# STM32.net
KiCad netlist of a schematic drawn in Altium Designer
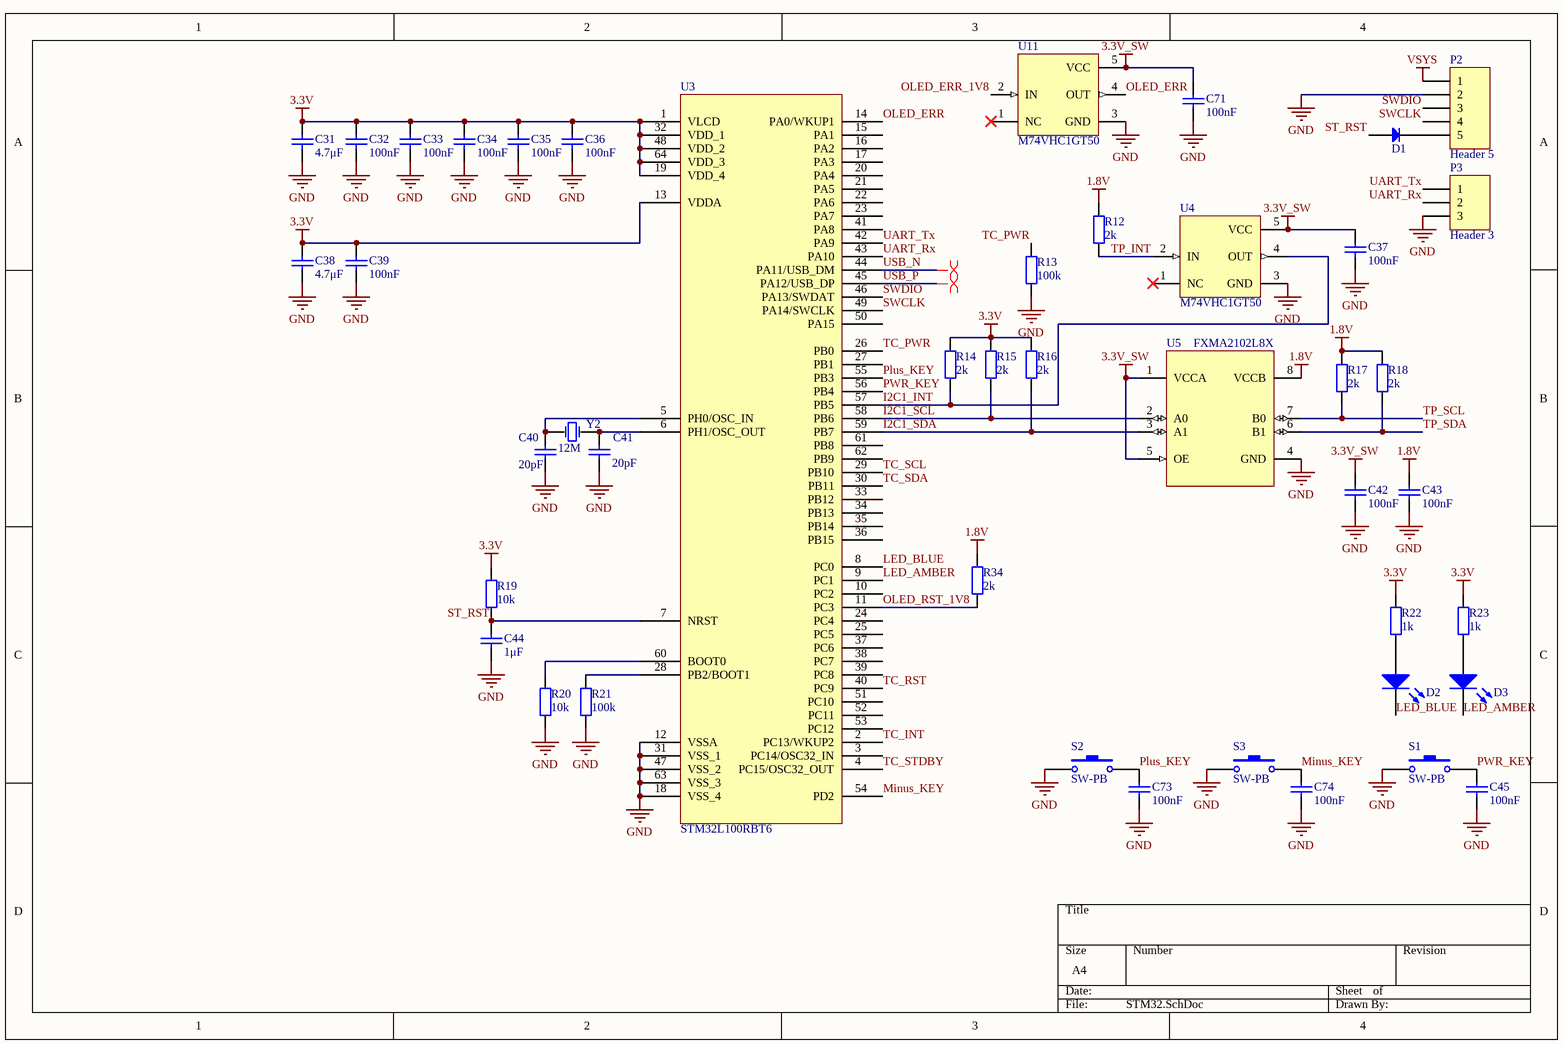
[diagram p0: STM32.SchDoc]

(export (version "E")
  (design (tool "Eeschema 10.0.6"))
  (components
    (comp (ref "C31")
      (value "4.7μF")
      (footprint "0402C")
      (description "无极性电容")
      (fields (field (name "Comment") "Cap") (field (name "PUBLISHER") "Altium Limited"))
      (libsource (lib "Huskie") (part "Cap"))
    )
    (comp (ref "C32")
      (value "100nF")
      (footprint "0402C")
      (description "无极性电容")
      (fields (field (name "Comment") "Cap") (field (name "PUBLISHER") "Altium Limited"))
      (libsource (lib "Huskie") (part "Cap"))
    )
    (comp (ref "C33")
      (value "100nF")
      (footprint "0402C")
      (description "无极性电容")
      (fields (field (name "Comment") "Cap") (field (name "PUBLISHER") "Altium Limited"))
      (libsource (lib "Huskie") (part "Cap"))
    )
    (comp (ref "C34")
      (value "100nF")
      (footprint "0402C")
      (description "无极性电容")
      (fields (field (name "Comment") "Cap") (field (name "PUBLISHER") "Altium Limited"))
      (libsource (lib "Huskie") (part "Cap"))
    )
    (comp (ref "C35")
      (value "100nF")
      (footprint "0402C")
      (description "无极性电容")
      (fields (field (name "Comment") "Cap") (field (name "PUBLISHER") "Altium Limited"))
      (libsource (lib "Huskie") (part "Cap"))
    )
    (comp (ref "C36")
      (value "100nF")
      (footprint "0402C")
      (description "无极性电容")
      (fields (field (name "Comment") "Cap") (field (name "PUBLISHER") "Altium Limited"))
      (libsource (lib "Huskie") (part "Cap"))
    )
    (comp (ref "C37")
      (value "100nF")
      (footprint "0402C")
      (description "无极性电容")
      (fields (field (name "Comment") "Cap") (field (name "PUBLISHER") "Altium Limited"))
      (libsource (lib "Huskie") (part "Cap"))
    )
    (comp (ref "C38")
      (value "4.7μF")
      (footprint "0402C")
      (description "无极性电容")
      (fields (field (name "Comment") "Cap") (field (name "PUBLISHER") "Altium Limited"))
      (libsource (lib "Huskie") (part "Cap"))
    )
    (comp (ref "C39")
      (value "100nF")
      (footprint "0402C")
      (description "无极性电容")
      (fields (field (name "Comment") "Cap") (field (name "PUBLISHER") "Altium Limited"))
      (libsource (lib "Huskie") (part "Cap"))
    )
    (comp (ref "C40")
      (value "20pF")
      (footprint "0402C")
      (description "无极性电容")
      (fields (field (name "Comment") "Cap") (field (name "PUBLISHER") "Altium Limited"))
      (libsource (lib "Huskie") (part "Cap"))
    )
    (comp (ref "C41")
      (value "20pF")
      (footprint "0402C")
      (description "无极性电容")
      (fields (field (name "Comment") "Cap") (field (name "PUBLISHER") "Altium Limited"))
      (libsource (lib "Huskie") (part "Cap"))
    )
    (comp (ref "C42")
      (value "100nF")
      (footprint "0402C")
      (description "无极性电容")
      (fields (field (name "Comment") "Cap") (field (name "PUBLISHER") "Altium Limited"))
      (libsource (lib "Huskie") (part "Cap"))
    )
    (comp (ref "C43")
      (value "100nF")
      (footprint "0402C")
      (description "无极性电容")
      (fields (field (name "Comment") "Cap") (field (name "PUBLISHER") "Altium Limited"))
      (libsource (lib "Huskie") (part "Cap"))
    )
    (comp (ref "C44")
      (value "1μF")
      (footprint "0402C")
      (description "无极性电容")
      (fields (field (name "Comment") "Cap") (field (name "PUBLISHER") "Altium Limited"))
      (libsource (lib "Huskie") (part "Cap"))
    )
    (comp (ref "C45")
      (value "100nF")
      (footprint "0402C")
      (description "无极性电容")
      (fields (field (name "Comment") "Cap") (field (name "PUBLISHER") "Altium Limited"))
      (libsource (lib "Huskie") (part "Cap"))
    )
    (comp (ref "C71")
      (value "100nF")
      (footprint "0402C")
      (description "无极性电容")
      (fields (field (name "Comment") "Cap") (field (name "PUBLISHER") "Altium Limited"))
      (libsource (lib "Huskie") (part "Cap"))
    )
    (comp (ref "C73")
      (value "100nF")
      (footprint "0402C")
      (description "无极性电容")
      (fields (field (name "Comment") "Cap") (field (name "PUBLISHER") "Altium Limited"))
      (libsource (lib "Huskie") (part "Cap"))
    )
    (comp (ref "C74")
      (value "100nF")
      (footprint "0402C")
      (description "无极性电容")
      (fields (field (name "Comment") "Cap") (field (name "PUBLISHER") "Altium Limited"))
      (libsource (lib "Huskie") (part "Cap"))
    )
    (comp (ref "D1")
      (value "Diode")
      (footprint "SOD-323")
      (description "二极管")
      (fields (field (name "PUBLISHER") "Altium Limited"))
      (libsource (lib "Huskie") (part "Diode"))
    )
    (comp (ref "D2")
      (value "LED0")
      (footprint "0603LED")
      (description "发光二极管")
      (fields (field (name "PUBLISHER") "Altium Limited"))
      (libsource (lib "Huskie") (part "LED0"))
    )
    (comp (ref "D3")
      (value "LED0")
      (footprint "0603LED")
      (description "发光二极管")
      (fields (field (name "PUBLISHER") "Altium Limited"))
      (libsource (lib "Huskie") (part "LED0"))
    )
    (comp (ref "P2")
      (value "Header 5")
      (footprint "HDR1X5")
      (description "Header, 5-Pin")
      (fields (field (name "PUBLISHER") "Altium Limited"))
      (libsource (lib "Miscellaneous Connectors") (part "Header 5"))
    )
    (comp (ref "P3")
      (value "Header 3")
      (footprint "HDR1X3")
      (description "Header, 3-Pin")
      (fields (field (name "PUBLISHER") "Altium Limited"))
      (libsource (lib "Miscellaneous Connectors") (part "Header 3"))
    )
    (comp (ref "R12")
      (value "2k")
      (footprint "0402R")
      (description "电阻")
      (fields (field (name "Comment") "Resistor") (field (name "PUBLISHER") "Altium Limited"))
      (libsource (lib "Huskie") (part "Resistor"))
    )
    (comp (ref "R13")
      (value "100k")
      (footprint "0402R")
      (description "电阻")
      (fields (field (name "Comment") "Resistor") (field (name "PUBLISHER") "Altium Limited"))
      (libsource (lib "Huskie") (part "Resistor"))
    )
    (comp (ref "R14")
      (value "2k")
      (footprint "0402R")
      (description "电阻")
      (fields (field (name "Comment") "Resistor") (field (name "PUBLISHER") "Altium Limited"))
      (libsource (lib "Huskie") (part "Resistor"))
    )
    (comp (ref "R15")
      (value "2k")
      (footprint "0402R")
      (description "电阻")
      (fields (field (name "Comment") "Resistor") (field (name "PUBLISHER") "Altium Limited"))
      (libsource (lib "Huskie") (part "Resistor"))
    )
    (comp (ref "R16")
      (value "2k")
      (footprint "0402R")
      (description "电阻")
      (fields (field (name "Comment") "Resistor") (field (name "PUBLISHER") "Altium Limited"))
      (libsource (lib "Huskie") (part "Resistor"))
    )
    (comp (ref "R17")
      (value "2k")
      (footprint "0402R")
      (description "电阻")
      (fields (field (name "Comment") "Resistor") (field (name "PUBLISHER") "Altium Limited"))
      (libsource (lib "Huskie") (part "Resistor"))
    )
    (comp (ref "R18")
      (value "2k")
      (footprint "0402R")
      (description "电阻")
      (fields (field (name "Comment") "Resistor") (field (name "PUBLISHER") "Altium Limited"))
      (libsource (lib "Huskie") (part "Resistor"))
    )
    (comp (ref "R19")
      (value "10k")
      (footprint "0402R")
      (description "电阻")
      (fields (field (name "Comment") "Resistor") (field (name "PUBLISHER") "Altium Limited"))
      (libsource (lib "Huskie") (part "Resistor"))
    )
    (comp (ref "R20")
      (value "10k")
      (footprint "0402R")
      (description "电阻")
      (fields (field (name "Comment") "Resistor") (field (name "PUBLISHER") "Altium Limited"))
      (libsource (lib "Huskie") (part "Resistor"))
    )
    (comp (ref "R21")
      (value "100k")
      (footprint "0402R")
      (description "电阻")
      (fields (field (name "Comment") "Resistor") (field (name "PUBLISHER") "Altium Limited"))
      (libsource (lib "Huskie") (part "Resistor"))
    )
    (comp (ref "R22")
      (value "1k")
      (footprint "0402R")
      (description "电阻")
      (fields (field (name "Comment") "Resistor") (field (name "PUBLISHER") "Altium Limited"))
      (libsource (lib "Huskie") (part "Resistor"))
    )
    (comp (ref "R23")
      (value "1k")
      (footprint "0402R")
      (description "电阻")
      (fields (field (name "Comment") "Resistor") (field (name "PUBLISHER") "Altium Limited"))
      (libsource (lib "Huskie") (part "Resistor"))
    )
    (comp (ref "R34")
      (value "2k")
      (footprint "0402R")
      (description "电阻")
      (fields (field (name "Comment") "Resistor") (field (name "PUBLISHER") "Altium Limited"))
      (libsource (lib "Huskie") (part "Resistor"))
    )
    (comp (ref "S1")
      (value "SW-PB")
      (footprint "SW-TS-TL3330E")
      (description "微动开关")
      (fields (field (name "PUBLISHER") "Altium Limited"))
      (libsource (lib "Huskie") (part "SW-PB"))
    )
    (comp (ref "S2")
      (value "SW-PB")
      (footprint "SW-TS-TL3330E")
      (description "微动开关")
      (fields (field (name "PUBLISHER") "Altium Limited"))
      (libsource (lib "Huskie") (part "SW-PB"))
    )
    (comp (ref "S3")
      (value "SW-PB")
      (footprint "SW-TS-TL3330E")
      (description "微动开关")
      (fields (field (name "PUBLISHER") "Altium Limited"))
      (libsource (lib "Huskie") (part "SW-PB"))
    )
    (comp (ref "U3")
      (value "STM32L100RBT6")
      (footprint "LQFP-64")
      (description "IC, STM32L MICROCONTROLLER, ARM CORTEX M3")
      (fields (field (name "MANUFACTURER") "ST MICROELECTRONICS"))
      (libsource (lib "Huskie") (part "STM32L100RBT6"))
    )
    (comp (ref "U4")
      (value "M74VHC1GT50")
      (footprint "SC-70(SC-70-5)")
      (description "IC, NON-INVERTING BUFFER, CMOS LOGIC LEVEL SHIFTER")
      (fields
        (field (name "MANUFACTURER") "ON SEMICONDUCTOR")
        (field (name "PART NUMBER") "M74VHC1GT50DFT2G")
      )
      (libsource (lib "Huskie") (part "M74VHC1GT50DFT2G"))
    )
    (comp (ref "U5")
      (value "FXMA2102L8X")
      (footprint "QFN-8_L1.6_W1.6")
      (description "IC, I2C TRANSLATOR, BUFFER AND REPEATER")
      (fields (field (name "MANUFACTURER") "FAIRCHILD SEMICONDUCTOR"))
      (libsource (lib "Huskie") (part "FXMA2102L8X"))
    )
    (comp (ref "U11")
      (value "M74VHC1GT50")
      (footprint "SC-70(SC-70-5)")
      (description "IC, NON-INVERTING BUFFER, CMOS LOGIC LEVEL SHIFTER")
      (fields
        (field (name "MANUFACTURER") "ON SEMICONDUCTOR")
        (field (name "PART NUMBER") "M74VHC1GT50DFT2G")
      )
      (libsource (lib "Huskie") (part "M74VHC1GT50DFT2G"))
    )
    (comp (ref "Y2")
      (value "12M")
      (footprint "XTAL_HC-49USX")
      (description "晶振")
      (fields (field (name "Comment") "XTAL") (field (name "PUBLISHER") "Altium Limited"))
      (libsource (lib "Huskie") (part "XTAL-2P"))
    )
  )
  (nets
    (net (code "1") (name "/I2C1_INT") (class "Default")
      (node (ref "R14") (pin "2") (pinfunction "2_2") (pintype "passive"))
      (node (ref "U3") (pin "57") (pinfunction "PB5_57") (pintype "passive"))
      (node (ref "U4") (pin "4") (pinfunction "OUT_4") (pintype "output"))
    )
    (net (code "2") (name "/I2C1_SCL") (class "Default")
      (node (ref "R15") (pin "2") (pinfunction "2_2") (pintype "passive"))
      (node (ref "U3") (pin "58") (pinfunction "PB6_58") (pintype "passive"))
      (node (ref "U5") (pin "2") (pinfunction "A0_2") (pintype "bidirectional"))
    )
    (net (code "3") (name "/I2C1_SDA") (class "Default")
      (node (ref "R16") (pin "2") (pinfunction "2_2") (pintype "passive"))
      (node (ref "U3") (pin "59") (pinfunction "PB7_59") (pintype "passive"))
      (node (ref "U5") (pin "3") (pinfunction "A1_3") (pintype "bidirectional"))
    )
    (net (code "4") (name "/LED_AMBER") (class "Default")
      (node (ref "D3") (pin "2") (pinfunction "K_2") (pintype "passive"))
      (node (ref "U3") (pin "9") (pinfunction "PC1_9") (pintype "passive"))
    )
    (net (code "5") (name "/LED_BLUE") (class "Default")
      (node (ref "D2") (pin "2") (pinfunction "K_2") (pintype "passive"))
      (node (ref "U3") (pin "8") (pinfunction "PC0_8") (pintype "passive"))
    )
    (net (code "6") (name "/Minus_KEY") (class "Default")
      (node (ref "C74") (pin "2") (pinfunction "2_2") (pintype "passive"))
      (node (ref "S3") (pin "2") (pinfunction "2_2") (pintype "passive"))
      (node (ref "U3") (pin "54") (pinfunction "PD2_54") (pintype "passive"))
    )
    (net (code "7") (name "/OLED_ERR") (class "Default")
      (node (ref "U11") (pin "4") (pinfunction "OUT_4") (pintype "output"))
      (node (ref "U3") (pin "14") (pinfunction "PA0/WKUP1_14") (pintype "passive"))
    )
    (net (code "8") (name "/OLED_ERR_1V8") (class "Default")
      (node (ref "U11") (pin "2") (pinfunction "IN_2") (pintype "input"))
    )
    (net (code "9") (name "/OLED_RST_1V8") (class "Default")
      (node (ref "R34") (pin "2") (pinfunction "2_2") (pintype "passive"))
      (node (ref "U3") (pin "11") (pinfunction "PC3_11") (pintype "passive"))
    )
    (net (code "10") (name "/PWR_KEY") (class "Default")
      (node (ref "C45") (pin "2") (pinfunction "2_2") (pintype "passive"))
      (node (ref "S1") (pin "2") (pinfunction "2_2") (pintype "passive"))
      (node (ref "U3") (pin "56") (pinfunction "PB4_56") (pintype "passive"))
    )
    (net (code "11") (name "/Plus_KEY") (class "Default")
      (node (ref "C73") (pin "2") (pinfunction "2_2") (pintype "passive"))
      (node (ref "S2") (pin "2") (pinfunction "2_2") (pintype "passive"))
      (node (ref "U3") (pin "55") (pinfunction "PB3_55") (pintype "passive"))
    )
    (net (code "12") (name "/ST_RST") (class "Default")
      (node (ref "C44") (pin "2") (pinfunction "2_2") (pintype "passive"))
      (node (ref "D1") (pin "1") (pinfunction "A_1") (pintype "passive"))
      (node (ref "R19") (pin "2") (pinfunction "2_2") (pintype "passive"))
      (node (ref "U3") (pin "7") (pinfunction "NRST_7") (pintype "passive"))
    )
    (net (code "13") (name "/SWCLK") (class "Default")
      (node (ref "P2") (pin "4") (pinfunction "4_4") (pintype "passive"))
      (node (ref "U3") (pin "49") (pinfunction "PA14/SWCLK_49") (pintype "passive"))
    )
    (net (code "14") (name "/SWDIO") (class "Default")
      (node (ref "P2") (pin "3") (pinfunction "3_3") (pintype "passive"))
      (node (ref "U3") (pin "46") (pinfunction "PA13/SWDAT_46") (pintype "passive"))
    )
    (net (code "15") (name "/TC_INT") (class "Default")
      (node (ref "U3") (pin "2") (pinfunction "PC13/WKUP2_2") (pintype "passive"))
    )
    (net (code "16") (name "/TC_PWR") (class "Default")
      (node (ref "R13") (pin "1") (pinfunction "1_1") (pintype "passive"))
      (node (ref "U3") (pin "26") (pinfunction "PB0_26") (pintype "passive"))
    )
    (net (code "17") (name "/TC_RST") (class "Default")
      (node (ref "U3") (pin "40") (pinfunction "PC9_40") (pintype "passive"))
    )
    (net (code "18") (name "/TC_SCL") (class "Default")
      (node (ref "U3") (pin "29") (pinfunction "PB10_29") (pintype "passive"))
    )
    (net (code "19") (name "/TC_SDA") (class "Default")
      (node (ref "U3") (pin "30") (pinfunction "PB11_30") (pintype "passive"))
    )
    (net (code "20") (name "/TC_STDBY") (class "Default")
      (node (ref "U3") (pin "4") (pinfunction "PC15/OSC32_OUT_4") (pintype "passive"))
    )
    (net (code "21") (name "/TP_INT") (class "Default")
      (node (ref "R12") (pin "2") (pinfunction "2_2") (pintype "passive"))
      (node (ref "U4") (pin "2") (pinfunction "IN_2") (pintype "input"))
    )
    (net (code "22") (name "/TP_SCL") (class "Default")
      (node (ref "R17") (pin "2") (pinfunction "2_2") (pintype "passive"))
      (node (ref "U5") (pin "7") (pinfunction "B0_7") (pintype "bidirectional"))
    )
    (net (code "23") (name "/TP_SDA") (class "Default")
      (node (ref "R18") (pin "2") (pinfunction "2_2") (pintype "passive"))
      (node (ref "U5") (pin "6") (pinfunction "B1_6") (pintype "bidirectional"))
    )
    (net (code "24") (name "/UART_Rx") (class "Default")
      (node (ref "P3") (pin "2") (pinfunction "2_2") (pintype "passive"))
      (node (ref "U3") (pin "43") (pinfunction "PA10_43") (pintype "passive"))
    )
    (net (code "25") (name "/UART_Tx") (class "Default")
      (node (ref "P3") (pin "1") (pinfunction "1_1") (pintype "passive"))
      (node (ref "U3") (pin "42") (pinfunction "PA9_42") (pintype "passive"))
    )
    (net (code "26") (name "/USB_N") (class "Default")
      (node (ref "U3") (pin "44") (pinfunction "PA11/USB_DM_44") (pintype "passive"))
    )
    (net (code "27") (name "/USB_P") (class "Default")
      (node (ref "U3") (pin "45") (pinfunction "PA12/USB_DP_45") (pintype "passive"))
    )
    (net (code "28") (name "1.8V") (class "Default")
      (node (ref "C43") (pin "2") (pinfunction "2_2") (pintype "passive"))
      (node (ref "R12") (pin "1") (pinfunction "1_1") (pintype "passive"))
      (node (ref "R17") (pin "1") (pinfunction "1_1") (pintype "passive"))
      (node (ref "R18") (pin "1") (pinfunction "1_1") (pintype "passive"))
      (node (ref "R34") (pin "1") (pinfunction "1_1") (pintype "passive"))
      (node (ref "U5") (pin "8") (pinfunction "VCCB_8") (pintype "power_in"))
    )
    (net (code "29") (name "3.3V") (class "Default")
      (node (ref "C31") (pin "2") (pinfunction "2_2") (pintype "passive"))
      (node (ref "C32") (pin "2") (pinfunction "2_2") (pintype "passive"))
      (node (ref "C33") (pin "2") (pinfunction "2_2") (pintype "passive"))
      (node (ref "C34") (pin "2") (pinfunction "2_2") (pintype "passive"))
      (node (ref "C35") (pin "2") (pinfunction "2_2") (pintype "passive"))
      (node (ref "C36") (pin "2") (pinfunction "2_2") (pintype "passive"))
      (node (ref "C38") (pin "2") (pinfunction "2_2") (pintype "passive"))
      (node (ref "C39") (pin "2") (pinfunction "2_2") (pintype "passive"))
      (node (ref "R14") (pin "1") (pinfunction "1_1") (pintype "passive"))
      (node (ref "R15") (pin "1") (pinfunction "1_1") (pintype "passive"))
      (node (ref "R16") (pin "1") (pinfunction "1_1") (pintype "passive"))
      (node (ref "R19") (pin "1") (pinfunction "1_1") (pintype "passive"))
      (node (ref "R22") (pin "1") (pinfunction "1_1") (pintype "passive"))
      (node (ref "R23") (pin "1") (pinfunction "1_1") (pintype "passive"))
      (node (ref "U3") (pin "1") (pinfunction "VLCD_1") (pintype "power_in"))
      (node (ref "U3") (pin "13") (pinfunction "VDDA_13") (pintype "power_in"))
      (node (ref "U3") (pin "19") (pinfunction "VDD_4_19") (pintype "power_in"))
      (node (ref "U3") (pin "32") (pinfunction "VDD_1_32") (pintype "power_in"))
      (node (ref "U3") (pin "48") (pinfunction "VDD_2_48") (pintype "power_in"))
      (node (ref "U3") (pin "64") (pinfunction "VDD_3_64") (pintype "power_in"))
    )
    (net (code "30") (name "3.3V_SW") (class "Default")
      (node (ref "C37") (pin "2") (pinfunction "2_2") (pintype "passive"))
      (node (ref "C42") (pin "2") (pinfunction "2_2") (pintype "passive"))
      (node (ref "C71") (pin "2") (pinfunction "2_2") (pintype "passive"))
      (node (ref "U11") (pin "5") (pinfunction "VCC_5") (pintype "power_in"))
      (node (ref "U4") (pin "5") (pinfunction "VCC_5") (pintype "power_in"))
      (node (ref "U5") (pin "1") (pinfunction "VCCA_1") (pintype "power_in"))
      (node (ref "U5") (pin "5") (pinfunction "OE_5") (pintype "input"))
    )
    (net (code "31") (name "GND") (class "Default")
      (node (ref "C31") (pin "1") (pinfunction "1_1") (pintype "passive"))
      (node (ref "C32") (pin "1") (pinfunction "1_1") (pintype "passive"))
      (node (ref "C33") (pin "1") (pinfunction "1_1") (pintype "passive"))
      (node (ref "C34") (pin "1") (pinfunction "1_1") (pintype "passive"))
      (node (ref "C35") (pin "1") (pinfunction "1_1") (pintype "passive"))
      (node (ref "C36") (pin "1") (pinfunction "1_1") (pintype "passive"))
      (node (ref "C37") (pin "1") (pinfunction "1_1") (pintype "passive"))
      (node (ref "C38") (pin "1") (pinfunction "1_1") (pintype "passive"))
      (node (ref "C39") (pin "1") (pinfunction "1_1") (pintype "passive"))
      (node (ref "C40") (pin "1") (pinfunction "1_1") (pintype "passive"))
      (node (ref "C41") (pin "1") (pinfunction "1_1") (pintype "passive"))
      (node (ref "C42") (pin "1") (pinfunction "1_1") (pintype "passive"))
      (node (ref "C43") (pin "1") (pinfunction "1_1") (pintype "passive"))
      (node (ref "C44") (pin "1") (pinfunction "1_1") (pintype "passive"))
      (node (ref "C45") (pin "1") (pinfunction "1_1") (pintype "passive"))
      (node (ref "C71") (pin "1") (pinfunction "1_1") (pintype "passive"))
      (node (ref "C73") (pin "1") (pinfunction "1_1") (pintype "passive"))
      (node (ref "C74") (pin "1") (pinfunction "1_1") (pintype "passive"))
      (node (ref "P2") (pin "2") (pinfunction "2_2") (pintype "passive"))
      (node (ref "P3") (pin "3") (pinfunction "3_3") (pintype "passive"))
      (node (ref "R13") (pin "2") (pinfunction "2_2") (pintype "passive"))
      (node (ref "R20") (pin "2") (pinfunction "2_2") (pintype "passive"))
      (node (ref "R21") (pin "2") (pinfunction "2_2") (pintype "passive"))
      (node (ref "S1") (pin "1") (pinfunction "1_1") (pintype "passive"))
      (node (ref "S2") (pin "1") (pinfunction "1_1") (pintype "passive"))
      (node (ref "S3") (pin "1") (pinfunction "1_1") (pintype "passive"))
      (node (ref "U11") (pin "3") (pinfunction "GND_3") (pintype "power_in"))
      (node (ref "U3") (pin "12") (pinfunction "VSSA_12") (pintype "power_in"))
      (node (ref "U3") (pin "18") (pinfunction "VSS_4_18") (pintype "power_in"))
      (node (ref "U3") (pin "31") (pinfunction "VSS_1_31") (pintype "power_in"))
      (node (ref "U3") (pin "47") (pinfunction "VSS_2_47") (pintype "power_in"))
      (node (ref "U3") (pin "63") (pinfunction "VSS_3_63") (pintype "power_in"))
      (node (ref "U4") (pin "3") (pinfunction "GND_3") (pintype "power_in"))
      (node (ref "U5") (pin "4") (pinfunction "GND_4") (pintype "power_in"))
    )
    (net (code "32") (name "Net-(D1-K)") (class "Default")
      (node (ref "D1") (pin "2") (pinfunction "K_2") (pintype "passive"))
      (node (ref "P2") (pin "5") (pinfunction "5_5") (pintype "passive"))
    )
    (net (code "33") (name "Net-(D2-A)") (class "Default")
      (node (ref "D2") (pin "1") (pinfunction "A_1") (pintype "passive"))
      (node (ref "R22") (pin "2") (pinfunction "2_2") (pintype "passive"))
    )
    (net (code "34") (name "Net-(D3-A)") (class "Default")
      (node (ref "D3") (pin "1") (pinfunction "A_1") (pintype "passive"))
      (node (ref "R23") (pin "2") (pinfunction "2_2") (pintype "passive"))
    )
    (net (code "35") (name "Net-(U3-BOOT0)") (class "Default")
      (node (ref "R20") (pin "1") (pinfunction "1_1") (pintype "passive"))
      (node (ref "U3") (pin "60") (pinfunction "BOOT0_60") (pintype "passive"))
    )
    (net (code "36") (name "Net-(U3-PB2{slash}BOOT1)") (class "Default")
      (node (ref "R21") (pin "1") (pinfunction "1_1") (pintype "passive"))
      (node (ref "U3") (pin "28") (pinfunction "PB2/BOOT1_28") (pintype "passive"))
    )
    (net (code "37") (name "Net-(U3-PH0{slash}OSC_IN)") (class "Default")
      (node (ref "C40") (pin "2") (pinfunction "2_2") (pintype "passive"))
      (node (ref "U3") (pin "5") (pinfunction "PH0/OSC_IN_5") (pintype "passive"))
      (node (ref "Y2") (pin "2") (pinfunction "OSC2_2") (pintype "passive"))
    )
    (net (code "38") (name "Net-(U3-PH1{slash}OSC_OUT)") (class "Default")
      (node (ref "C41") (pin "2") (pinfunction "2_2") (pintype "passive"))
      (node (ref "U3") (pin "6") (pinfunction "PH1/OSC_OUT_6") (pintype "passive"))
      (node (ref "Y2") (pin "1") (pinfunction "OSC1_1") (pintype "passive"))
    )
    (net (code "39") (name "VSYS") (class "Default")
      (node (ref "P2") (pin "1") (pinfunction "1_1") (pintype "passive"))
    )
    (net (code "40") (name "unconnected-(U3-PA1-Pad15)") (class "Default")
      (node (ref "U3") (pin "15") (pinfunction "PA1_15") (pintype "passive"))
    )
    (net (code "41") (name "unconnected-(U3-PA2-Pad16)") (class "Default")
      (node (ref "U3") (pin "16") (pinfunction "PA2_16") (pintype "passive"))
    )
    (net (code "42") (name "unconnected-(U3-PA3-Pad17)") (class "Default")
      (node (ref "U3") (pin "17") (pinfunction "PA3_17") (pintype "passive"))
    )
    (net (code "43") (name "unconnected-(U3-PA4-Pad20)") (class "Default")
      (node (ref "U3") (pin "20") (pinfunction "PA4_20") (pintype "passive"))
    )
    (net (code "44") (name "unconnected-(U3-PA5-Pad21)") (class "Default")
      (node (ref "U3") (pin "21") (pinfunction "PA5_21") (pintype "passive"))
    )
    (net (code "45") (name "unconnected-(U3-PA6-Pad22)") (class "Default")
      (node (ref "U3") (pin "22") (pinfunction "PA6_22") (pintype "passive"))
    )
    (net (code "46") (name "unconnected-(U3-PA7-Pad23)") (class "Default")
      (node (ref "U3") (pin "23") (pinfunction "PA7_23") (pintype "passive"))
    )
    (net (code "47") (name "unconnected-(U3-PA8-Pad41)") (class "Default")
      (node (ref "U3") (pin "41") (pinfunction "PA8_41") (pintype "passive"))
    )
    (net (code "48") (name "unconnected-(U3-PA15-Pad50)") (class "Default")
      (node (ref "U3") (pin "50") (pinfunction "PA15_50") (pintype "passive"))
    )
    (net (code "49") (name "unconnected-(U3-PB1-Pad27)") (class "Default")
      (node (ref "U3") (pin "27") (pinfunction "PB1_27") (pintype "passive"))
    )
    (net (code "50") (name "unconnected-(U3-PB8-Pad61)") (class "Default")
      (node (ref "U3") (pin "61") (pinfunction "PB8_61") (pintype "passive"))
    )
    (net (code "51") (name "unconnected-(U3-PB9-Pad62)") (class "Default")
      (node (ref "U3") (pin "62") (pinfunction "PB9_62") (pintype "passive"))
    )
    (net (code "52") (name "unconnected-(U3-PB12-Pad33)") (class "Default")
      (node (ref "U3") (pin "33") (pinfunction "PB12_33") (pintype "passive"))
    )
    (net (code "53") (name "unconnected-(U3-PB13-Pad34)") (class "Default")
      (node (ref "U3") (pin "34") (pinfunction "PB13_34") (pintype "passive"))
    )
    (net (code "54") (name "unconnected-(U3-PB14-Pad35)") (class "Default")
      (node (ref "U3") (pin "35") (pinfunction "PB14_35") (pintype "passive"))
    )
    (net (code "55") (name "unconnected-(U3-PB15-Pad36)") (class "Default")
      (node (ref "U3") (pin "36") (pinfunction "PB15_36") (pintype "passive"))
    )
    (net (code "56") (name "unconnected-(U3-PC2-Pad10)") (class "Default")
      (node (ref "U3") (pin "10") (pinfunction "PC2_10") (pintype "passive"))
    )
    (net (code "57") (name "unconnected-(U3-PC4-Pad24)") (class "Default")
      (node (ref "U3") (pin "24") (pinfunction "PC4_24") (pintype "passive"))
    )
    (net (code "58") (name "unconnected-(U3-PC5-Pad25)") (class "Default")
      (node (ref "U3") (pin "25") (pinfunction "PC5_25") (pintype "passive"))
    )
    (net (code "59") (name "unconnected-(U3-PC6-Pad37)") (class "Default")
      (node (ref "U3") (pin "37") (pinfunction "PC6_37") (pintype "passive"))
    )
    (net (code "60") (name "unconnected-(U3-PC7-Pad38)") (class "Default")
      (node (ref "U3") (pin "38") (pinfunction "PC7_38") (pintype "passive"))
    )
    (net (code "61") (name "unconnected-(U3-PC8-Pad39)") (class "Default")
      (node (ref "U3") (pin "39") (pinfunction "PC8_39") (pintype "passive"))
    )
    (net (code "62") (name "unconnected-(U3-PC10-Pad51)") (class "Default")
      (node (ref "U3") (pin "51") (pinfunction "PC10_51") (pintype "passive"))
    )
    (net (code "63") (name "unconnected-(U3-PC11-Pad52)") (class "Default")
      (node (ref "U3") (pin "52") (pinfunction "PC11_52") (pintype "passive"))
    )
    (net (code "64") (name "unconnected-(U3-PC12-Pad53)") (class "Default")
      (node (ref "U3") (pin "53") (pinfunction "PC12_53") (pintype "passive"))
    )
    (net (code "65") (name "unconnected-(U3-PC14{slash}OSC32_IN-Pad3)") (class "Default")
      (node (ref "U3") (pin "3") (pinfunction "PC14/OSC32_IN_3") (pintype "passive"))
    )
    (net (code "66") (name "unconnected-(U4-NC-Pad1)") (class "Default")
      (node (ref "U4") (pin "1") (pinfunction "NC_1") (pintype "power_in+no_connect"))
    )
    (net (code "67") (name "unconnected-(U11-NC-Pad1)") (class "Default")
      (node (ref "U11") (pin "1") (pinfunction "NC_1") (pintype "power_in+no_connect"))
    )
  )
)
